# lab4.net
KiCad netlist of a schematic drawn in EAGLE
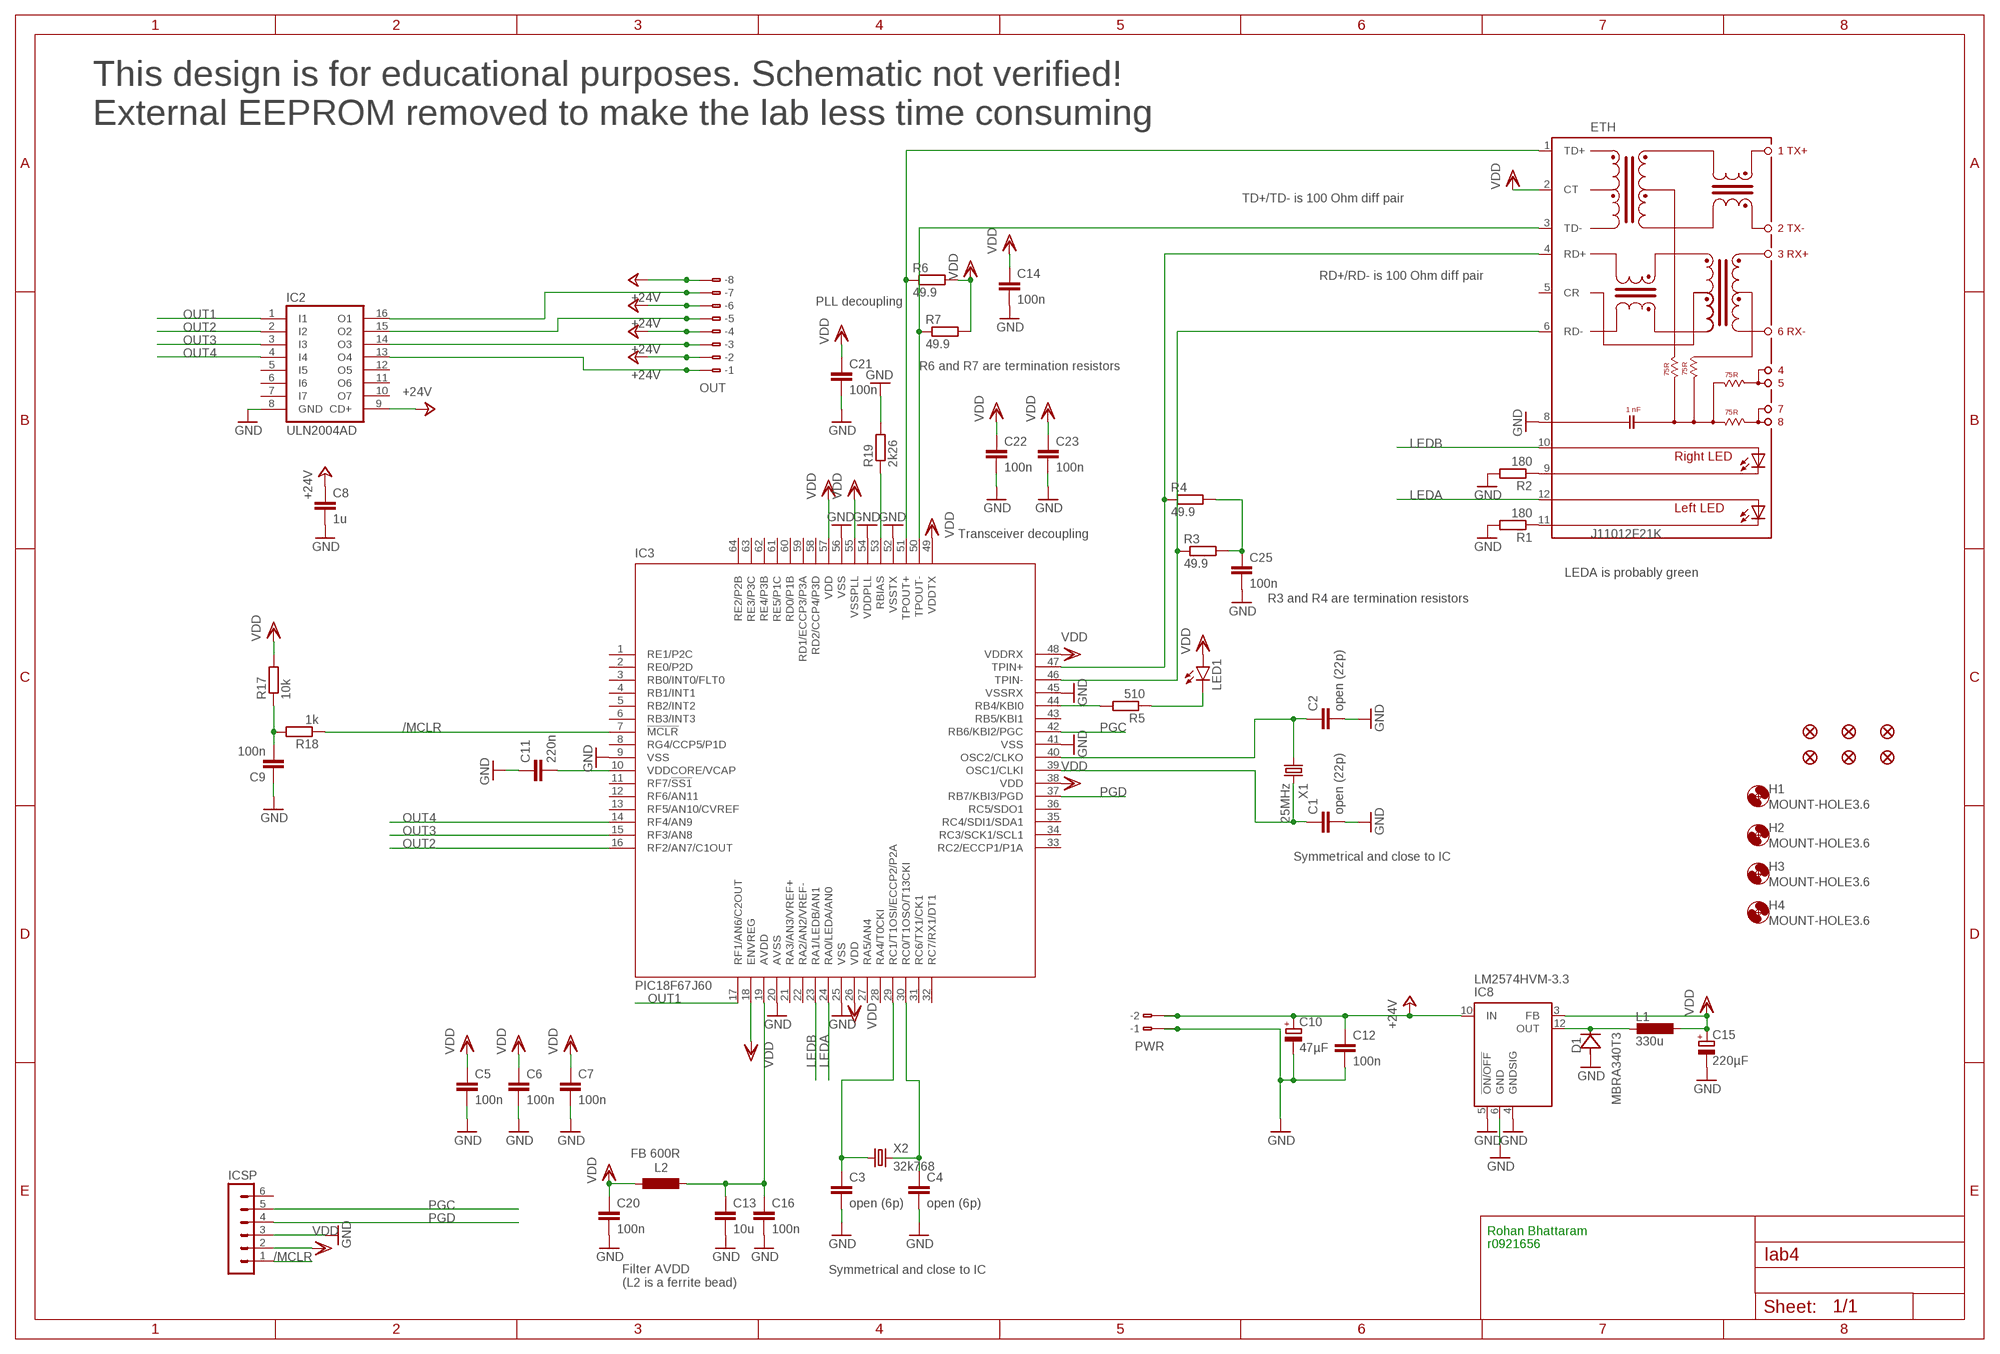
[diagram p0: schematic, sheet 1]

(export (version "E")
  (design (tool "Eeschema 10.0.6"))
  (components
    (comp (ref "C1")
      (value "open (22p)")
      (footprint "eagle-import:C0603")
      (fields (field (name "SPICEPREFIX") "C"))
      (libsource (lib "eagle-import") (part "C-EUC0603"))
    )
    (comp (ref "C2")
      (value "open (22p)")
      (footprint "eagle-import:C0603")
      (fields (field (name "SPICEPREFIX") "C"))
      (libsource (lib "eagle-import") (part "C-EUC0603"))
    )
    (comp (ref "C3")
      (value "open (6p)")
      (footprint "eagle-import:C0603")
      (fields (field (name "SPICEPREFIX") "C"))
      (libsource (lib "eagle-import") (part "C-EUC0603"))
    )
    (comp (ref "C4")
      (value "open (6p)")
      (footprint "eagle-import:C0603")
      (fields (field (name "SPICEPREFIX") "C"))
      (libsource (lib "eagle-import") (part "C-EUC0603"))
    )
    (comp (ref "C5")
      (value "100n")
      (footprint "eagle-import:C0603")
      (fields (field (name "SPICEPREFIX") "C"))
      (libsource (lib "eagle-import") (part "C-EUC0603"))
    )
    (comp (ref "C6")
      (value "100n")
      (footprint "eagle-import:C0603")
      (fields (field (name "SPICEPREFIX") "C"))
      (libsource (lib "eagle-import") (part "C-EUC0603"))
    )
    (comp (ref "C7")
      (value "100n")
      (footprint "eagle-import:C0603")
      (fields (field (name "SPICEPREFIX") "C"))
      (libsource (lib "eagle-import") (part "C-EUC0603"))
    )
    (comp (ref "C8")
      (value "1u")
      (footprint "eagle-import:C0603")
      (libsource (lib "eagle-import") (part "C-EUC0603"))
    )
    (comp (ref "C9")
      (value "100n")
      (footprint "eagle-import:C0603")
      (libsource (lib "eagle-import") (part "C-EUC0603"))
    )
    (comp (ref "C10")
      (value "47µF")
      (footprint "eagle-import:E2,5-5")
      (libsource (lib "eagle-import") (part "CPOL-EUE2.5-5"))
    )
    (comp (ref "C11")
      (value "220n")
      (footprint "eagle-import:C0603")
      (fields (field (name "SPICEPREFIX") "C"))
      (libsource (lib "eagle-import") (part "C-EUC0603"))
    )
    (comp (ref "C12")
      (value "100n")
      (footprint "eagle-import:C0603")
      (libsource (lib "eagle-import") (part "C-EUC0603"))
    )
    (comp (ref "C13")
      (value "10u")
      (footprint "eagle-import:C0805")
      (libsource (lib "eagle-import") (part "rcl_C-EUC0805"))
    )
    (comp (ref "C14")
      (value "100n")
      (footprint "eagle-import:C0603")
      (fields (field (name "SPICEPREFIX") "C"))
      (libsource (lib "eagle-import") (part "C-EUC0603"))
    )
    (comp (ref "C15")
      (value "220µF")
      (footprint "eagle-import:E2,5-5")
      (libsource (lib "eagle-import") (part "CPOL-EUE2.5-5"))
    )
    (comp (ref "C16")
      (value "100n")
      (footprint "eagle-import:C0603")
      (fields (field (name "SPICEPREFIX") "C"))
      (libsource (lib "eagle-import") (part "C-EUC0603"))
    )
    (comp (ref "C20")
      (value "100n")
      (footprint "eagle-import:C0603")
      (fields (field (name "SPICEPREFIX") "C"))
      (libsource (lib "eagle-import") (part "C-EUC0603"))
    )
    (comp (ref "C21")
      (value "100n")
      (footprint "eagle-import:C0603")
      (fields (field (name "SPICEPREFIX") "C"))
      (libsource (lib "eagle-import") (part "C-EUC0603"))
    )
    (comp (ref "C22")
      (value "100n")
      (footprint "eagle-import:C0603")
      (fields (field (name "SPICEPREFIX") "C"))
      (libsource (lib "eagle-import") (part "C-EUC0603"))
    )
    (comp (ref "C23")
      (value "100n")
      (footprint "eagle-import:C0603")
      (fields (field (name "SPICEPREFIX") "C"))
      (libsource (lib "eagle-import") (part "C-EUC0603"))
    )
    (comp (ref "C25")
      (value "100n")
      (footprint "eagle-import:C0603")
      (fields (field (name "SPICEPREFIX") "C"))
      (libsource (lib "eagle-import") (part "C-EUC0603"))
    )
    (comp (ref "D1")
      (value "MBRA340T3")
      (footprint "eagle-import:SMA")
      (libsource (lib "eagle-import") (part "MBRA340T3"))
    )
    (comp (ref "ETH")
      (value "J11012F21K")
      (footprint "eagle-import:J1")
      (libsource (lib "eagle-import") (part "J11012F21K"))
    )
    (comp (ref "FID1")
      (value "FIDUCIAL\"\"")
      (footprint "eagle-import:FIDUCIAL_1MM")
      (libsource (lib "eagle-import") (part "FIDUCIAL{dblquote}{dblquote}"))
    )
    (comp (ref "FID2")
      (value "FIDUCIAL\"\"")
      (footprint "eagle-import:FIDUCIAL_1MM")
      (libsource (lib "eagle-import") (part "FIDUCIAL{dblquote}{dblquote}"))
    )
    (comp (ref "FID3")
      (value "FIDUCIAL\"\"")
      (footprint "eagle-import:FIDUCIAL_1MM")
      (libsource (lib "eagle-import") (part "FIDUCIAL{dblquote}{dblquote}"))
    )
    (comp (ref "FID4")
      (value "FIDUCIAL\"\"")
      (footprint "eagle-import:FIDUCIAL_1MM")
      (libsource (lib "eagle-import") (part "FIDUCIAL{dblquote}{dblquote}"))
    )
    (comp (ref "FID5")
      (value "FIDUCIAL\"\"")
      (footprint "eagle-import:FIDUCIAL_1MM")
      (libsource (lib "eagle-import") (part "FIDUCIAL{dblquote}{dblquote}"))
    )
    (comp (ref "FID6")
      (value "FIDUCIAL\"\"")
      (footprint "eagle-import:FIDUCIAL_1MM")
      (libsource (lib "eagle-import") (part "FIDUCIAL{dblquote}{dblquote}"))
    )
    (comp (ref "H1")
      (value "MOUNT-HOLE3.6")
      (footprint "eagle-import:3,6")
      (libsource (lib "eagle-import") (part "MOUNT-HOLE3.6"))
    )
    (comp (ref "H2")
      (value "MOUNT-HOLE3.6")
      (footprint "eagle-import:3,6")
      (libsource (lib "eagle-import") (part "MOUNT-HOLE3.6"))
    )
    (comp (ref "H3")
      (value "MOUNT-HOLE3.6")
      (footprint "eagle-import:3,6")
      (libsource (lib "eagle-import") (part "MOUNT-HOLE3.6"))
    )
    (comp (ref "H4")
      (value "MOUNT-HOLE3.6")
      (footprint "eagle-import:3,6")
      (libsource (lib "eagle-import") (part "MOUNT-HOLE3.6"))
    )
    (comp (ref "IC2")
      (value "ULN2004AD")
      (footprint "eagle-import:SO16")
      (libsource (lib "eagle-import") (part "ULN2004AD"))
    )
    (comp (ref "IC3")
      (value "PIC18F67J60")
      (footprint "eagle-import:TQFP64-10X10")
      (fields (field (name "MPN") "PIC18F67J60-I/PT"))
      (libsource (lib "eagle-import") (part "PIC18F6J607"))
    )
    (comp (ref "IC8")
      (value "LM2574HVM-3.3")
      (footprint "eagle-import:SO14W")
      (libsource (lib "eagle-import") (part "LM2574?-HVM3.3"))
    )
    (comp (ref "ICSP")
      (value "MA06-1")
      (footprint "eagle-import:MA06-1")
      (libsource (lib "eagle-import") (part "MA06-1"))
    )
    (comp (ref "L1")
      (value "330u")
      (footprint "eagle-import:SRN8040TA")
      (libsource (lib "eagle-import") (part "SRN8040TA"))
    )
    (comp (ref "L2")
      (value "FB 600R")
      (footprint "eagle-import:RESC1608X80N")
      (libsource (lib "eagle-import") (part "L-EUL0603"))
    )
    (comp (ref "LED1")
      (value "LEDCHIP-LED0805")
      (footprint "eagle-import:CHIP-LED0805")
      (libsource (lib "eagle-import") (part "LEDCHIP-LED0805"))
    )
    (comp (ref "OUT")
      (value "233-108")
      (footprint "eagle-import:233-108")
      (libsource (lib "eagle-import") (part "233-108"))
    )
    (comp (ref "PWR")
      (value "233-102")
      (footprint "eagle-import:233-102")
      (libsource (lib "eagle-import") (part "233-102"))
    )
    (comp (ref "R1")
      (value "180")
      (footprint "eagle-import:R0603")
      (libsource (lib "eagle-import") (part "R-EU_R0603"))
    )
    (comp (ref "R2")
      (value "180")
      (footprint "eagle-import:R0603")
      (libsource (lib "eagle-import") (part "R-EU_R0603"))
    )
    (comp (ref "R3")
      (value "49.9")
      (footprint "eagle-import:R0603")
      (libsource (lib "eagle-import") (part "R-EU_R0603"))
    )
    (comp (ref "R4")
      (value "49.9")
      (footprint "eagle-import:R0603")
      (libsource (lib "eagle-import") (part "R-EU_R0603"))
    )
    (comp (ref "R5")
      (value "510")
      (footprint "eagle-import:R0603")
      (libsource (lib "eagle-import") (part "R-EU_R0603"))
    )
    (comp (ref "R6")
      (value "49.9")
      (footprint "eagle-import:R0603")
      (libsource (lib "eagle-import") (part "R-EU_R0603"))
    )
    (comp (ref "R7")
      (value "49.9")
      (footprint "eagle-import:R0603")
      (libsource (lib "eagle-import") (part "R-EU_R0603"))
    )
    (comp (ref "R17")
      (value "10k")
      (footprint "eagle-import:R0603")
      (libsource (lib "eagle-import") (part "R-EU_R0603"))
    )
    (comp (ref "R18")
      (value "1k")
      (footprint "eagle-import:R0603")
      (libsource (lib "eagle-import") (part "R-EU_R0603"))
    )
    (comp (ref "R19")
      (value "2k26")
      (footprint "eagle-import:R0603")
      (libsource (lib "eagle-import") (part "R-EU_R0603"))
    )
    (comp (ref "X1")
      (value "25MHz")
      (footprint "eagle-import:CTS406")
      (libsource (lib "eagle-import") (part "crystal_204_CRYSTALCTS406"))
    )
    (comp (ref "X2")
      (value "32k768")
      (footprint "eagle-import:TC26V")
      (libsource (lib "eagle-import") (part "CRYSTALTC26V"))
    )
  )
  (nets
    (net (code "1") (name "+24V") (class "Default")
      (node (ref "C10") (pin "+") (pinfunction "+_+") (pintype "passive"))
      (node (ref "C12") (pin "1") (pinfunction "1_1") (pintype "passive"))
      (node (ref "C8") (pin "1") (pinfunction "1_1") (pintype "passive"))
      (node (ref "IC2") (pin "9") (pinfunction "CD+_9") (pintype "passive"))
      (node (ref "IC8") (pin "10") (pinfunction "IN_10") (pintype "input"))
      (node (ref "OUT") (pin "A2") (pinfunction "-2_A2") (pintype "passive"))
      (node (ref "OUT") (pin "A4") (pinfunction "-4_A4") (pintype "passive"))
      (node (ref "OUT") (pin "A6") (pinfunction "-6_A6") (pintype "passive"))
      (node (ref "OUT") (pin "A8") (pinfunction "-8_A8") (pintype "passive"))
      (node (ref "OUT") (pin "B2") (pinfunction "B-2_B2") (pintype "passive"))
      (node (ref "OUT") (pin "B4") (pinfunction "B-4_B4") (pintype "passive"))
      (node (ref "OUT") (pin "B6") (pinfunction "B-6_B6") (pintype "passive"))
      (node (ref "OUT") (pin "B8") (pinfunction "B-8_B8") (pintype "passive"))
      (node (ref "PWR") (pin "A2") (pinfunction "-2_A2") (pintype "passive"))
      (node (ref "PWR") (pin "B2") (pinfunction "B-2_B2") (pintype "passive"))
    )
    (net (code "2") (name "/LEDA") (class "Default")
      (node (ref "ETH") (pin "12") (pinfunction "A-L_12") (pintype "passive"))
      (node (ref "IC3") (pin "24") (pinfunction "RA0/LEDA/AN0_24") (pintype "bidirectional"))
    )
    (net (code "3") (name "/LEDB") (class "Default")
      (node (ref "ETH") (pin "10") (pinfunction "A-R_10") (pintype "passive"))
      (node (ref "IC3") (pin "23") (pinfunction "RA1/LEDB/AN1_23") (pintype "bidirectional"))
    )
    (net (code "4") (name "/OUT1") (class "Default")
      (node (ref "IC2") (pin "1") (pinfunction "I1_1") (pintype "input"))
      (node (ref "IC3") (pin "17") (pinfunction "RF1/AN6/C2OUT_17") (pintype "bidirectional"))
    )
    (net (code "5") (name "/OUT2") (class "Default")
      (node (ref "IC2") (pin "2") (pinfunction "I2_2") (pintype "input"))
      (node (ref "IC3") (pin "16") (pinfunction "RF2/AN7/C1OUT_16") (pintype "bidirectional"))
    )
    (net (code "6") (name "/OUT3") (class "Default")
      (node (ref "IC2") (pin "3") (pinfunction "I3_3") (pintype "input"))
      (node (ref "IC3") (pin "15") (pinfunction "RF3/AN8_15") (pintype "bidirectional"))
    )
    (net (code "7") (name "/OUT4") (class "Default")
      (node (ref "IC2") (pin "4") (pinfunction "I4_4") (pintype "input"))
      (node (ref "IC3") (pin "14") (pinfunction "RF4/AN9_14") (pintype "bidirectional"))
    )
    (net (code "8") (name "/PGC") (class "Default")
      (node (ref "IC3") (pin "42") (pinfunction "RB6/KBI2/PGC_42") (pintype "bidirectional"))
      (node (ref "ICSP") (pin "5") (pinfunction "5_5") (pintype "passive"))
    )
    (net (code "9") (name "/PGD") (class "Default")
      (node (ref "IC3") (pin "37") (pinfunction "RB7/KBI3/PGD_37") (pintype "bidirectional"))
      (node (ref "ICSP") (pin "4") (pinfunction "4_4") (pintype "passive"))
    )
    (net (code "10") (name "/{slash}MCLR") (class "Default")
      (node (ref "IC3") (pin "7") (pinfunction "~{MCLR}_7") (pintype "bidirectional"))
      (node (ref "ICSP") (pin "1") (pinfunction "1_1") (pintype "passive"))
      (node (ref "R18") (pin "1") (pinfunction "1_1") (pintype "passive"))
    )
    (net (code "11") (name "GND") (class "Default")
      (node (ref "C1") (pin "2") (pinfunction "2_2") (pintype "passive"))
      (node (ref "C10") (pin "-") (pinfunction "-_-") (pintype "passive"))
      (node (ref "C11") (pin "1") (pinfunction "1_1") (pintype "passive"))
      (node (ref "C12") (pin "2") (pinfunction "2_2") (pintype "passive"))
      (node (ref "C13") (pin "2") (pinfunction "2_2") (pintype "passive"))
      (node (ref "C14") (pin "2") (pinfunction "2_2") (pintype "passive"))
      (node (ref "C15") (pin "-") (pinfunction "-_-") (pintype "passive"))
      (node (ref "C16") (pin "2") (pinfunction "2_2") (pintype "passive"))
      (node (ref "C2") (pin "2") (pinfunction "2_2") (pintype "passive"))
      (node (ref "C20") (pin "2") (pinfunction "2_2") (pintype "passive"))
      (node (ref "C21") (pin "2") (pinfunction "2_2") (pintype "passive"))
      (node (ref "C22") (pin "2") (pinfunction "2_2") (pintype "passive"))
      (node (ref "C23") (pin "2") (pinfunction "2_2") (pintype "passive"))
      (node (ref "C25") (pin "2") (pinfunction "2_2") (pintype "passive"))
      (node (ref "C3") (pin "2") (pinfunction "2_2") (pintype "passive"))
      (node (ref "C4") (pin "2") (pinfunction "2_2") (pintype "passive"))
      (node (ref "C5") (pin "2") (pinfunction "2_2") (pintype "passive"))
      (node (ref "C6") (pin "2") (pinfunction "2_2") (pintype "passive"))
      (node (ref "C7") (pin "2") (pinfunction "2_2") (pintype "passive"))
      (node (ref "C8") (pin "2") (pinfunction "2_2") (pintype "passive"))
      (node (ref "C9") (pin "1") (pinfunction "1_1") (pintype "passive"))
      (node (ref "D1") (pin "A") (pinfunction "A_A") (pintype "passive"))
      (node (ref "ETH") (pin "8") (pinfunction "8_8") (pintype "input"))
      (node (ref "IC2") (pin "8") (pinfunction "GND_8") (pintype "power_in"))
      (node (ref "IC3") (pin "20") (pinfunction "AVSS_20") (pintype "bidirectional"))
      (node (ref "IC3") (pin "25") (pinfunction "VSS_25") (pintype "bidirectional"))
      (node (ref "IC3") (pin "41") (pinfunction "VSS_41") (pintype "bidirectional"))
      (node (ref "IC3") (pin "45") (pinfunction "VSSRX_45") (pintype "bidirectional"))
      (node (ref "IC3") (pin "52") (pinfunction "VSSTX_52") (pintype "bidirectional"))
      (node (ref "IC3") (pin "54") (pinfunction "VDDPLL_54") (pintype "bidirectional"))
      (node (ref "IC3") (pin "56") (pinfunction "VSS_56") (pintype "bidirectional"))
      (node (ref "IC3") (pin "9") (pinfunction "VSS_9") (pintype "bidirectional"))
      (node (ref "IC8") (pin "4") (pinfunction "GNDSIG_4") (pintype "input"))
      (node (ref "IC8") (pin "5") (pinfunction "~{ON/OFF}_5") (pintype "input"))
      (node (ref "IC8") (pin "6") (pinfunction "GND_6") (pintype "power_in"))
      (node (ref "ICSP") (pin "3") (pinfunction "3_3") (pintype "passive"))
      (node (ref "PWR") (pin "A1") (pinfunction "-1_A1") (pintype "passive"))
      (node (ref "PWR") (pin "B1") (pinfunction "B-1_B1") (pintype "passive"))
      (node (ref "R1") (pin "2") (pinfunction "2_2") (pintype "passive"))
      (node (ref "R19") (pin "2") (pinfunction "2_2") (pintype "passive"))
      (node (ref "R2") (pin "2") (pinfunction "2_2") (pintype "passive"))
    )
    (net (code "12") (name "Net-(C9-Pad2)") (class "Default")
      (node (ref "C9") (pin "2") (pinfunction "2_2") (pintype "passive"))
      (node (ref "R17") (pin "1") (pinfunction "1_1") (pintype "passive"))
      (node (ref "R18") (pin "2") (pinfunction "2_2") (pintype "passive"))
    )
    (net (code "13") (name "Net-(C25-Pad1)") (class "Default")
      (node (ref "C25") (pin "1") (pinfunction "1_1") (pintype "passive"))
      (node (ref "R3") (pin "2") (pinfunction "2_2") (pintype "passive"))
      (node (ref "R4") (pin "2") (pinfunction "2_2") (pintype "passive"))
    )
    (net (code "14") (name "Net-(ETH-C-L)") (class "Default")
      (node (ref "ETH") (pin "11") (pinfunction "C-L_11") (pintype "passive"))
      (node (ref "R1") (pin "1") (pinfunction "1_1") (pintype "passive"))
    )
    (net (code "15") (name "Net-(ETH-C-R)") (class "Default")
      (node (ref "ETH") (pin "9") (pinfunction "C-R_9") (pintype "passive"))
      (node (ref "R2") (pin "1") (pinfunction "1_1") (pintype "passive"))
    )
    (net (code "16") (name "Net-(ETH-RD+)") (class "Default")
      (node (ref "ETH") (pin "4") (pinfunction "RD+_4") (pintype "input"))
      (node (ref "IC3") (pin "47") (pinfunction "TPIN+_47") (pintype "bidirectional"))
      (node (ref "R4") (pin "1") (pinfunction "1_1") (pintype "passive"))
    )
    (net (code "17") (name "Net-(ETH-RD-)") (class "Default")
      (node (ref "ETH") (pin "6") (pinfunction "RD-_6") (pintype "input"))
      (node (ref "IC3") (pin "46") (pinfunction "TPIN-_46") (pintype "bidirectional"))
      (node (ref "R3") (pin "1") (pinfunction "1_1") (pintype "passive"))
    )
    (net (code "18") (name "Net-(ETH-TD+)") (class "Default")
      (node (ref "ETH") (pin "1") (pinfunction "TD+_1") (pintype "input"))
      (node (ref "IC3") (pin "51") (pinfunction "TPOUT+_51") (pintype "bidirectional"))
      (node (ref "R6") (pin "1") (pinfunction "1_1") (pintype "passive"))
    )
    (net (code "19") (name "Net-(ETH-TD-)") (class "Default")
      (node (ref "ETH") (pin "3") (pinfunction "TD-_3") (pintype "input"))
      (node (ref "IC3") (pin "50") (pinfunction "TPOUT-_50") (pintype "bidirectional"))
      (node (ref "R7") (pin "1") (pinfunction "1_1") (pintype "passive"))
    )
    (net (code "20") (name "Net-(IC2-O1)") (class "Default")
      (node (ref "IC2") (pin "16") (pinfunction "O1_16") (pintype "open_collector"))
      (node (ref "OUT") (pin "A7") (pinfunction "-7_A7") (pintype "passive"))
      (node (ref "OUT") (pin "B7") (pinfunction "B-7_B7") (pintype "passive"))
    )
    (net (code "21") (name "Net-(IC2-O2)") (class "Default")
      (node (ref "IC2") (pin "15") (pinfunction "O2_15") (pintype "open_collector"))
      (node (ref "OUT") (pin "A5") (pinfunction "-5_A5") (pintype "passive"))
      (node (ref "OUT") (pin "B5") (pinfunction "B-5_B5") (pintype "passive"))
    )
    (net (code "22") (name "Net-(IC2-O3)") (class "Default")
      (node (ref "IC2") (pin "14") (pinfunction "O3_14") (pintype "open_collector"))
      (node (ref "OUT") (pin "A3") (pinfunction "-3_A3") (pintype "passive"))
      (node (ref "OUT") (pin "B3") (pinfunction "B-3_B3") (pintype "passive"))
    )
    (net (code "23") (name "Net-(IC2-O4)") (class "Default")
      (node (ref "IC2") (pin "13") (pinfunction "O4_13") (pintype "open_collector"))
      (node (ref "OUT") (pin "A1") (pinfunction "-1_A1") (pintype "passive"))
      (node (ref "OUT") (pin "B1") (pinfunction "B-1_B1") (pintype "passive"))
    )
    (net (code "24") (name "Net-(IC3-AVDD)") (class "Default")
      (node (ref "C13") (pin "1") (pinfunction "1_1") (pintype "passive"))
      (node (ref "C16") (pin "1") (pinfunction "1_1") (pintype "passive"))
      (node (ref "IC3") (pin "19") (pinfunction "AVDD_19") (pintype "bidirectional"))
      (node (ref "L2") (pin "1") (pinfunction "1_1") (pintype "passive"))
    )
    (net (code "25") (name "Net-(IC3-OSC1{slash}CLKI)") (class "Default")
      (node (ref "C1") (pin "1") (pinfunction "1_1") (pintype "passive"))
      (node (ref "IC3") (pin "39") (pinfunction "OSC1/CLKI_39") (pintype "bidirectional"))
      (node (ref "X1") (pin "3") (pinfunction "2_3") (pintype "passive"))
    )
    (net (code "26") (name "Net-(IC3-OSC2{slash}CLKO)") (class "Default")
      (node (ref "C2") (pin "1") (pinfunction "1_1") (pintype "passive"))
      (node (ref "IC3") (pin "40") (pinfunction "OSC2/CLKO_40") (pintype "bidirectional"))
      (node (ref "X1") (pin "1") (pinfunction "1_1") (pintype "passive"))
    )
    (net (code "27") (name "Net-(IC3-RB4{slash}KBI0)") (class "Default")
      (node (ref "IC3") (pin "44") (pinfunction "RB4/KBI0_44") (pintype "bidirectional"))
      (node (ref "R5") (pin "2") (pinfunction "2_2") (pintype "passive"))
    )
    (net (code "28") (name "Net-(IC3-RBIAS)") (class "Default")
      (node (ref "IC3") (pin "53") (pinfunction "RBIAS_53") (pintype "bidirectional"))
      (node (ref "R19") (pin "1") (pinfunction "1_1") (pintype "passive"))
    )
    (net (code "29") (name "Net-(IC3-RC0{slash}T1OSO{slash}T13CKI)") (class "Default")
      (node (ref "C4") (pin "1") (pinfunction "1_1") (pintype "passive"))
      (node (ref "IC3") (pin "30") (pinfunction "RC0/T1OSO/T13CKI_30") (pintype "bidirectional"))
      (node (ref "X2") (pin "2") (pinfunction "2_2") (pintype "passive"))
    )
    (net (code "30") (name "Net-(IC3-RC1{slash}T1OSI{slash}ECCP2{slash}P2A)") (class "Default")
      (node (ref "C3") (pin "1") (pinfunction "1_1") (pintype "passive"))
      (node (ref "IC3") (pin "29") (pinfunction "RC1/T1OSI/ECCP2/P2A_29") (pintype "bidirectional"))
      (node (ref "X2") (pin "1") (pinfunction "1_1") (pintype "passive"))
    )
    (net (code "31") (name "Net-(IC3-VDDCORE{slash}VCAP)") (class "Default")
      (node (ref "C11") (pin "2") (pinfunction "2_2") (pintype "passive"))
      (node (ref "IC3") (pin "10") (pinfunction "VDDCORE/VCAP_10") (pintype "bidirectional"))
    )
    (net (code "32") (name "Net-(IC8-OUT)") (class "Default")
      (node (ref "D1") (pin "C") (pinfunction "C_C") (pintype "passive"))
      (node (ref "IC8") (pin "12") (pinfunction "OUT_12") (pintype "passive"))
      (node (ref "L1") (pin "1") (pinfunction "1_1") (pintype "passive"))
    )
    (net (code "33") (name "Net-(LED1-PadC)") (class "Default")
      (node (ref "LED1") (pin "C") (pinfunction "C_C") (pintype "passive"))
      (node (ref "R5") (pin "1") (pinfunction "1_1") (pintype "passive"))
    )
    (net (code "34") (name "VDD") (class "Default")
      (node (ref "C14") (pin "1") (pinfunction "1_1") (pintype "passive"))
      (node (ref "C15") (pin "+") (pinfunction "+_+") (pintype "passive"))
      (node (ref "C20") (pin "1") (pinfunction "1_1") (pintype "passive"))
      (node (ref "C21") (pin "1") (pinfunction "1_1") (pintype "passive"))
      (node (ref "C22") (pin "1") (pinfunction "1_1") (pintype "passive"))
      (node (ref "C23") (pin "1") (pinfunction "1_1") (pintype "passive"))
      (node (ref "C5") (pin "1") (pinfunction "1_1") (pintype "passive"))
      (node (ref "C6") (pin "1") (pinfunction "1_1") (pintype "passive"))
      (node (ref "C7") (pin "1") (pinfunction "1_1") (pintype "passive"))
      (node (ref "ETH") (pin "2") (pinfunction "CT_2") (pintype "input"))
      (node (ref "IC3") (pin "18") (pinfunction "ENVREG_18") (pintype "bidirectional"))
      (node (ref "IC3") (pin "26") (pinfunction "VDD_26") (pintype "bidirectional"))
      (node (ref "IC3") (pin "38") (pinfunction "VDD_38") (pintype "bidirectional"))
      (node (ref "IC3") (pin "48") (pinfunction "VDDRX_48") (pintype "bidirectional"))
      (node (ref "IC3") (pin "49") (pinfunction "VDDTX_49") (pintype "bidirectional"))
      (node (ref "IC3") (pin "55") (pinfunction "VSSPLL_55") (pintype "bidirectional"))
      (node (ref "IC3") (pin "57") (pinfunction "VDD_57") (pintype "bidirectional"))
      (node (ref "IC8") (pin "3") (pinfunction "FB_3") (pintype "input"))
      (node (ref "ICSP") (pin "2") (pinfunction "2_2") (pintype "passive"))
      (node (ref "L1") (pin "2") (pinfunction "2_2") (pintype "passive"))
      (node (ref "L2") (pin "2") (pinfunction "2_2") (pintype "passive"))
      (node (ref "LED1") (pin "A") (pinfunction "A_A") (pintype "passive"))
      (node (ref "R17") (pin "2") (pinfunction "2_2") (pintype "passive"))
      (node (ref "R6") (pin "2") (pinfunction "2_2") (pintype "passive"))
      (node (ref "R7") (pin "2") (pinfunction "2_2") (pintype "passive"))
    )
    (net (code "35") (name "unconnected-(ETH-CR-Pad5)") (class "Default")
      (node (ref "ETH") (pin "5") (pinfunction "CR_5") (pintype "input"))
    )
    (net (code "36") (name "unconnected-(IC2-I5-Pad5)") (class "Default")
      (node (ref "IC2") (pin "5") (pinfunction "I5_5") (pintype "input"))
    )
    (net (code "37") (name "unconnected-(IC2-I6-Pad6)") (class "Default")
      (node (ref "IC2") (pin "6") (pinfunction "I6_6") (pintype "input"))
    )
    (net (code "38") (name "unconnected-(IC2-I7-Pad7)") (class "Default")
      (node (ref "IC2") (pin "7") (pinfunction "I7_7") (pintype "input"))
    )
    (net (code "39") (name "unconnected-(IC2-O5-Pad12)") (class "Default")
      (node (ref "IC2") (pin "12") (pinfunction "O5_12") (pintype "open_collector"))
    )
    (net (code "40") (name "unconnected-(IC2-O6-Pad11)") (class "Default")
      (node (ref "IC2") (pin "11") (pinfunction "O6_11") (pintype "open_collector"))
    )
    (net (code "41") (name "unconnected-(IC2-O7-Pad10)") (class "Default")
      (node (ref "IC2") (pin "10") (pinfunction "O7_10") (pintype "open_collector"))
    )
    (net (code "42") (name "unconnected-(IC3-RA2{slash}AN2{slash}VREF--Pad22)") (class "Default")
      (node (ref "IC3") (pin "22") (pinfunction "RA2/AN2/VREF-_22") (pintype "bidirectional"))
    )
    (net (code "43") (name "unconnected-(IC3-RA3{slash}AN3{slash}VREF+-Pad21)") (class "Default")
      (node (ref "IC3") (pin "21") (pinfunction "RA3/AN3/VREF+_21") (pintype "bidirectional"))
    )
    (net (code "44") (name "unconnected-(IC3-RA4{slash}T0CKI-Pad28)") (class "Default")
      (node (ref "IC3") (pin "28") (pinfunction "RA4/T0CKI_28") (pintype "bidirectional"))
    )
    (net (code "45") (name "unconnected-(IC3-RA5{slash}AN4-Pad27)") (class "Default")
      (node (ref "IC3") (pin "27") (pinfunction "RA5/AN4_27") (pintype "bidirectional"))
    )
    (net (code "46") (name "unconnected-(IC3-RB0{slash}INT0{slash}FLT0-Pad3)") (class "Default")
      (node (ref "IC3") (pin "3") (pinfunction "RB0/INT0/FLT0_3") (pintype "bidirectional"))
    )
    (net (code "47") (name "unconnected-(IC3-RB1{slash}INT1-Pad4)") (class "Default")
      (node (ref "IC3") (pin "4") (pinfunction "RB1/INT1_4") (pintype "bidirectional"))
    )
    (net (code "48") (name "unconnected-(IC3-RB2{slash}INT2-Pad5)") (class "Default")
      (node (ref "IC3") (pin "5") (pinfunction "RB2/INT2_5") (pintype "bidirectional"))
    )
    (net (code "49") (name "unconnected-(IC3-RB3{slash}INT3-Pad6)") (class "Default")
      (node (ref "IC3") (pin "6") (pinfunction "RB3/INT3_6") (pintype "bidirectional"))
    )
    (net (code "50") (name "unconnected-(IC3-RB5{slash}KBI1-Pad43)") (class "Default")
      (node (ref "IC3") (pin "43") (pinfunction "RB5/KBI1_43") (pintype "bidirectional"))
    )
    (net (code "51") (name "unconnected-(IC3-RC2{slash}ECCP1{slash}P1A-Pad33)") (class "Default")
      (node (ref "IC3") (pin "33") (pinfunction "RC2/ECCP1/P1A_33") (pintype "bidirectional"))
    )
    (net (code "52") (name "unconnected-(IC3-RC3{slash}SCK1{slash}SCL1-Pad34)") (class "Default")
      (node (ref "IC3") (pin "34") (pinfunction "RC3/SCK1/SCL1_34") (pintype "bidirectional"))
    )
    (net (code "53") (name "unconnected-(IC3-RC4{slash}SDI1{slash}SDA1-Pad35)") (class "Default")
      (node (ref "IC3") (pin "35") (pinfunction "RC4/SDI1/SDA1_35") (pintype "bidirectional"))
    )
    (net (code "54") (name "unconnected-(IC3-RC5{slash}SDO1-Pad36)") (class "Default")
      (node (ref "IC3") (pin "36") (pinfunction "RC5/SDO1_36") (pintype "bidirectional"))
    )
    (net (code "55") (name "unconnected-(IC3-RC6{slash}TX1{slash}CK1-Pad31)") (class "Default")
      (node (ref "IC3") (pin "31") (pinfunction "RC6/TX1/CK1_31") (pintype "bidirectional"))
    )
    (net (code "56") (name "unconnected-(IC3-RC7{slash}RX1{slash}DT1-Pad32)") (class "Default")
      (node (ref "IC3") (pin "32") (pinfunction "RC7/RX1/DT1_32") (pintype "bidirectional"))
    )
    (net (code "57") (name "unconnected-(IC3-RD0{slash}P1B-Pad60)") (class "Default")
      (node (ref "IC3") (pin "60") (pinfunction "RD0/P1B_60") (pintype "bidirectional"))
    )
    (net (code "58") (name "unconnected-(IC3-RD1{slash}ECCP3{slash}P3A-Pad59)") (class "Default")
      (node (ref "IC3") (pin "59") (pinfunction "RD1/ECCP3/P3A_59") (pintype "bidirectional"))
    )
    (net (code "59") (name "unconnected-(IC3-RD2{slash}CCP4{slash}P3D-Pad58)") (class "Default")
      (node (ref "IC3") (pin "58") (pinfunction "RD2/CCP4/P3D_58") (pintype "bidirectional"))
    )
    (net (code "60") (name "unconnected-(IC3-RE0{slash}P2D-Pad2)") (class "Default")
      (node (ref "IC3") (pin "2") (pinfunction "RE0/P2D_2") (pintype "bidirectional"))
    )
    (net (code "61") (name "unconnected-(IC3-RE1{slash}P2C-Pad1)") (class "Default")
      (node (ref "IC3") (pin "1") (pinfunction "RE1/P2C_1") (pintype "bidirectional"))
    )
    (net (code "62") (name "unconnected-(IC3-RE2{slash}P2B-Pad64)") (class "Default")
      (node (ref "IC3") (pin "64") (pinfunction "RE2/P2B_64") (pintype "bidirectional"))
    )
    (net (code "63") (name "unconnected-(IC3-RE3{slash}P3C-Pad63)") (class "Default")
      (node (ref "IC3") (pin "63") (pinfunction "RE3/P3C_63") (pintype "bidirectional"))
    )
    (net (code "64") (name "unconnected-(IC3-RE4{slash}P3B-Pad62)") (class "Default")
      (node (ref "IC3") (pin "62") (pinfunction "RE4/P3B_62") (pintype "bidirectional"))
    )
    (net (code "65") (name "unconnected-(IC3-RE5{slash}P1C-Pad61)") (class "Default")
      (node (ref "IC3") (pin "61") (pinfunction "RE5/P1C_61") (pintype "bidirectional"))
    )
    (net (code "66") (name "unconnected-(IC3-RF5{slash}AN10{slash}CVREF-Pad13)") (class "Default")
      (node (ref "IC3") (pin "13") (pinfunction "RF5/AN10/CVREF_13") (pintype "bidirectional"))
    )
    (net (code "67") (name "unconnected-(IC3-RF6{slash}AN11-Pad12)") (class "Default")
      (node (ref "IC3") (pin "12") (pinfunction "RF6/AN11_12") (pintype "bidirectional"))
    )
    (net (code "68") (name "unconnected-(IC3-RF7{slash}~{SS1}-Pad11)") (class "Default")
      (node (ref "IC3") (pin "11") (pinfunction "RF7/~{SS1}_11") (pintype "bidirectional"))
    )
    (net (code "69") (name "unconnected-(IC3-RG4{slash}CCP5{slash}P1D-Pad8)") (class "Default")
      (node (ref "IC3") (pin "8") (pinfunction "RG4/CCP5/P1D_8") (pintype "bidirectional"))
    )
    (net (code "70") (name "unconnected-(ICSP-Pad6)") (class "Default")
      (node (ref "ICSP") (pin "6") (pinfunction "6_6") (pintype "passive"))
    )
  )
)
